# EndStop.net
KiCad netlist of a schematic drawn in EAGLE
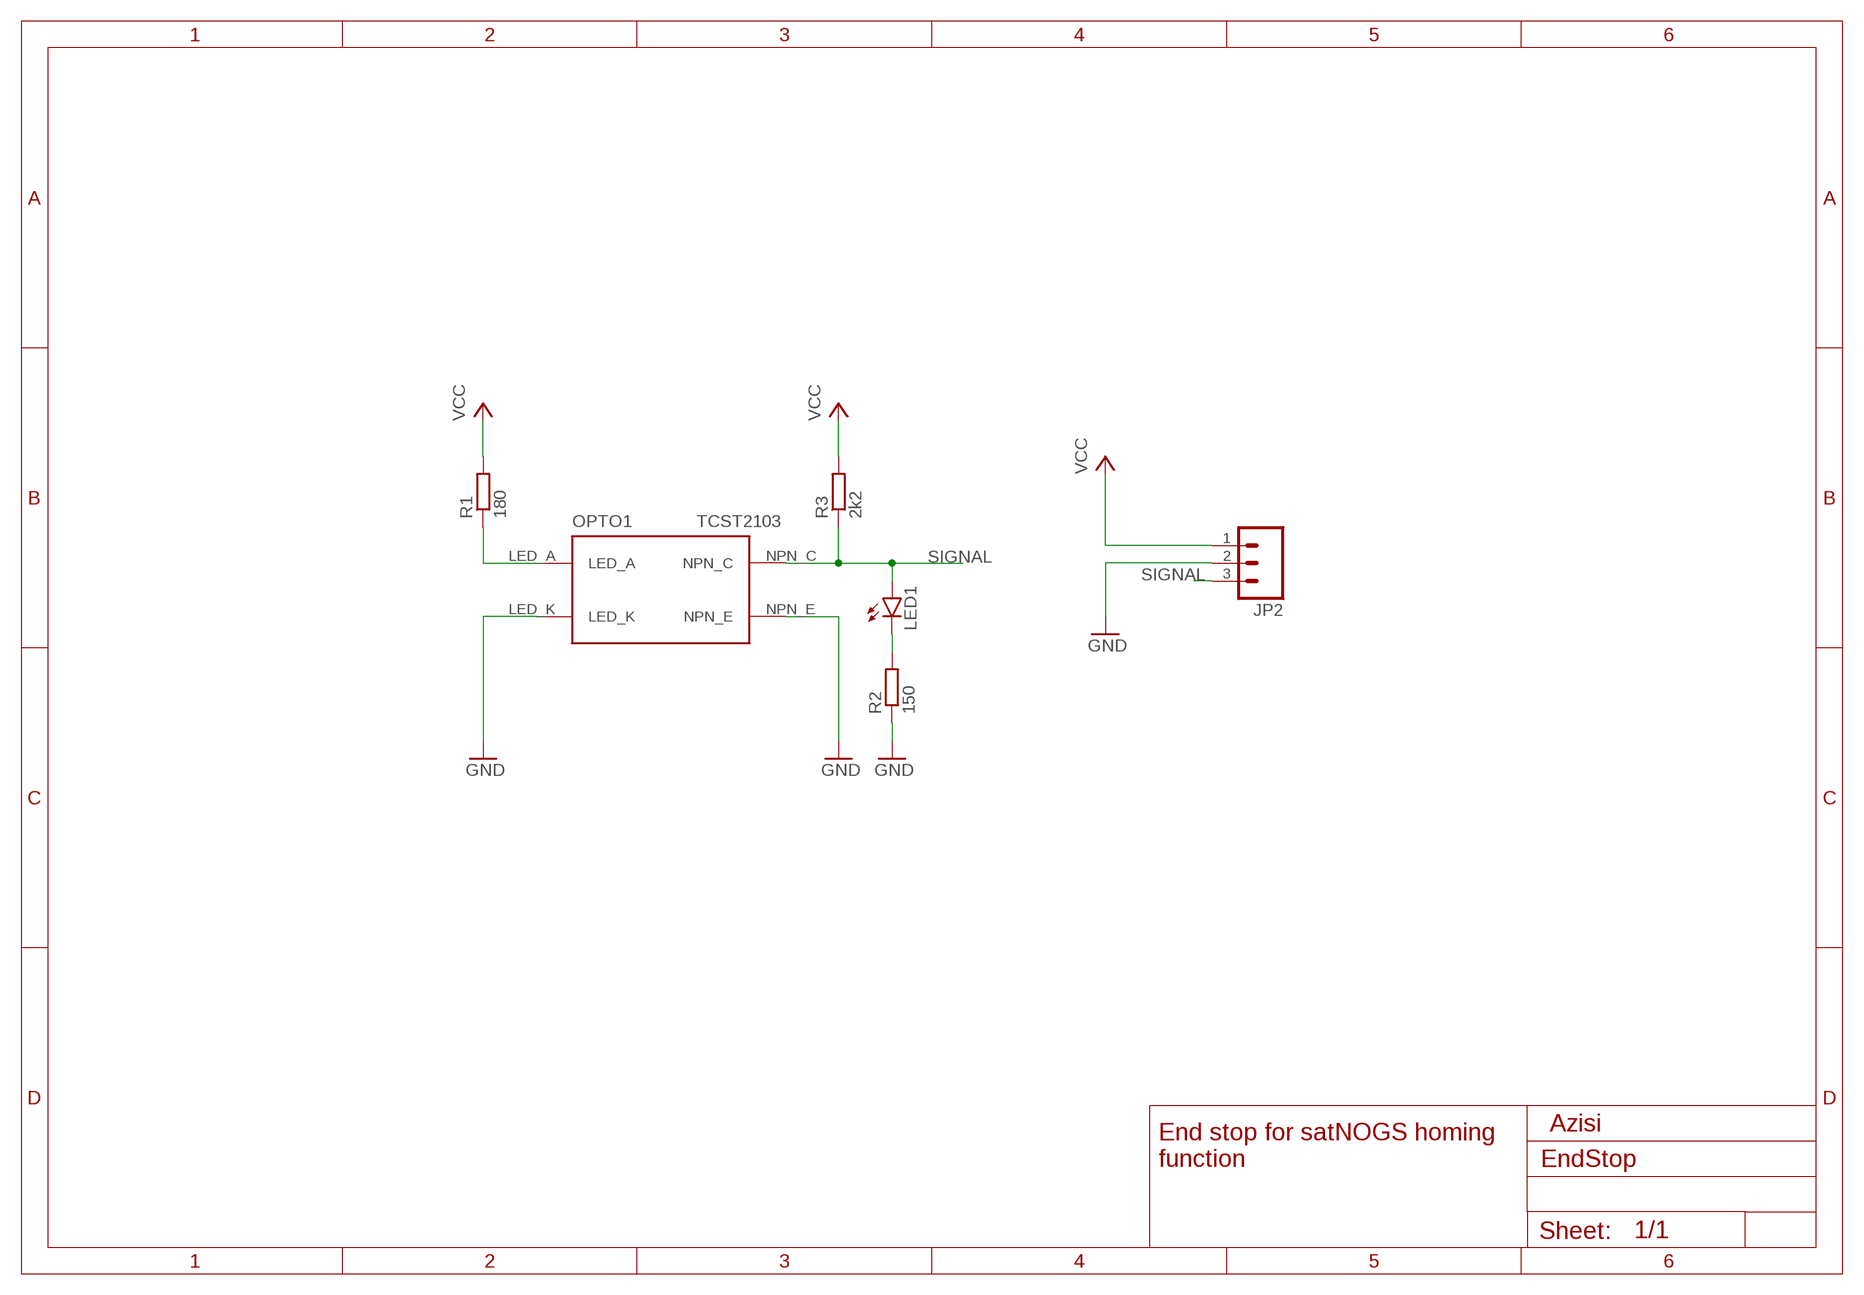
[diagram p0: schematic, sheet 1]

(export (version "E")
  (design (tool "Eeschema 10.0.6"))
  (components
    (comp (ref "JP2")
      (value "M03PTH")
      (footprint "eagle-import:1X03")
      (libsource (lib "eagle-import") (part "M03PTH"))
    )
    (comp (ref "LED1")
      (value "LED3MM")
      (footprint "eagle-import:LED3MM")
      (libsource (lib "eagle-import") (part "LED3MM"))
    )
    (comp (ref "OPTO1")
      (value "TCST2103")
      (footprint "eagle-import:TCST2013")
      (libsource (lib "eagle-import") (part "TCST2103"))
    )
    (comp (ref "R1")
      (value "180")
      (footprint "eagle-import:M0805")
      (libsource (lib "eagle-import") (part "R-EU_M0805"))
    )
    (comp (ref "R2")
      (value "150")
      (footprint "eagle-import:M0805")
      (libsource (lib "eagle-import") (part "R-EU_M0805"))
    )
    (comp (ref "R3")
      (value "2k2")
      (footprint "eagle-import:M0805")
      (libsource (lib "eagle-import") (part "R-EU_M0805"))
    )
  )
  (nets
    (net (code "1") (name "/SIGNAL") (class "Default")
      (node (ref "JP2") (pin "3") (pinfunction "3_3") (pintype "passive"))
      (node (ref "LED1") (pin "A") (pinfunction "A_A") (pintype "passive"))
      (node (ref "OPTO1") (pin "NPN_C") (pinfunction "NPN_C_NPN_C") (pintype "bidirectional"))
      (node (ref "R3") (pin "1") (pinfunction "1_1") (pintype "passive"))
    )
    (net (code "2") (name "GND") (class "Default")
      (node (ref "JP2") (pin "2") (pinfunction "2_2") (pintype "passive"))
      (node (ref "OPTO1") (pin "LED_K") (pinfunction "LED_K_LED_K") (pintype "bidirectional"))
      (node (ref "OPTO1") (pin "NPN_E") (pinfunction "NPN_E_NPN_E") (pintype "bidirectional"))
      (node (ref "R2") (pin "1") (pinfunction "1_1") (pintype "passive"))
    )
    (net (code "3") (name "Net-(LED1-C)") (class "Default")
      (node (ref "LED1") (pin "K") (pinfunction "C_K") (pintype "passive"))
      (node (ref "R2") (pin "2") (pinfunction "2_2") (pintype "passive"))
    )
    (net (code "4") (name "Net-(OPTO1-PadLED_A)") (class "Default")
      (node (ref "OPTO1") (pin "LED_A") (pinfunction "LED_A_LED_A") (pintype "bidirectional"))
      (node (ref "R1") (pin "1") (pinfunction "1_1") (pintype "passive"))
    )
    (net (code "5") (name "VCC") (class "Default")
      (node (ref "JP2") (pin "1") (pinfunction "1_1") (pintype "passive"))
      (node (ref "R1") (pin "2") (pinfunction "2_2") (pintype "passive"))
      (node (ref "R3") (pin "2") (pinfunction "2_2") (pintype "passive"))
    )
  )
)
